# Sheet_1.net
KiCad netlist of a schematic drawn in EasyEDA
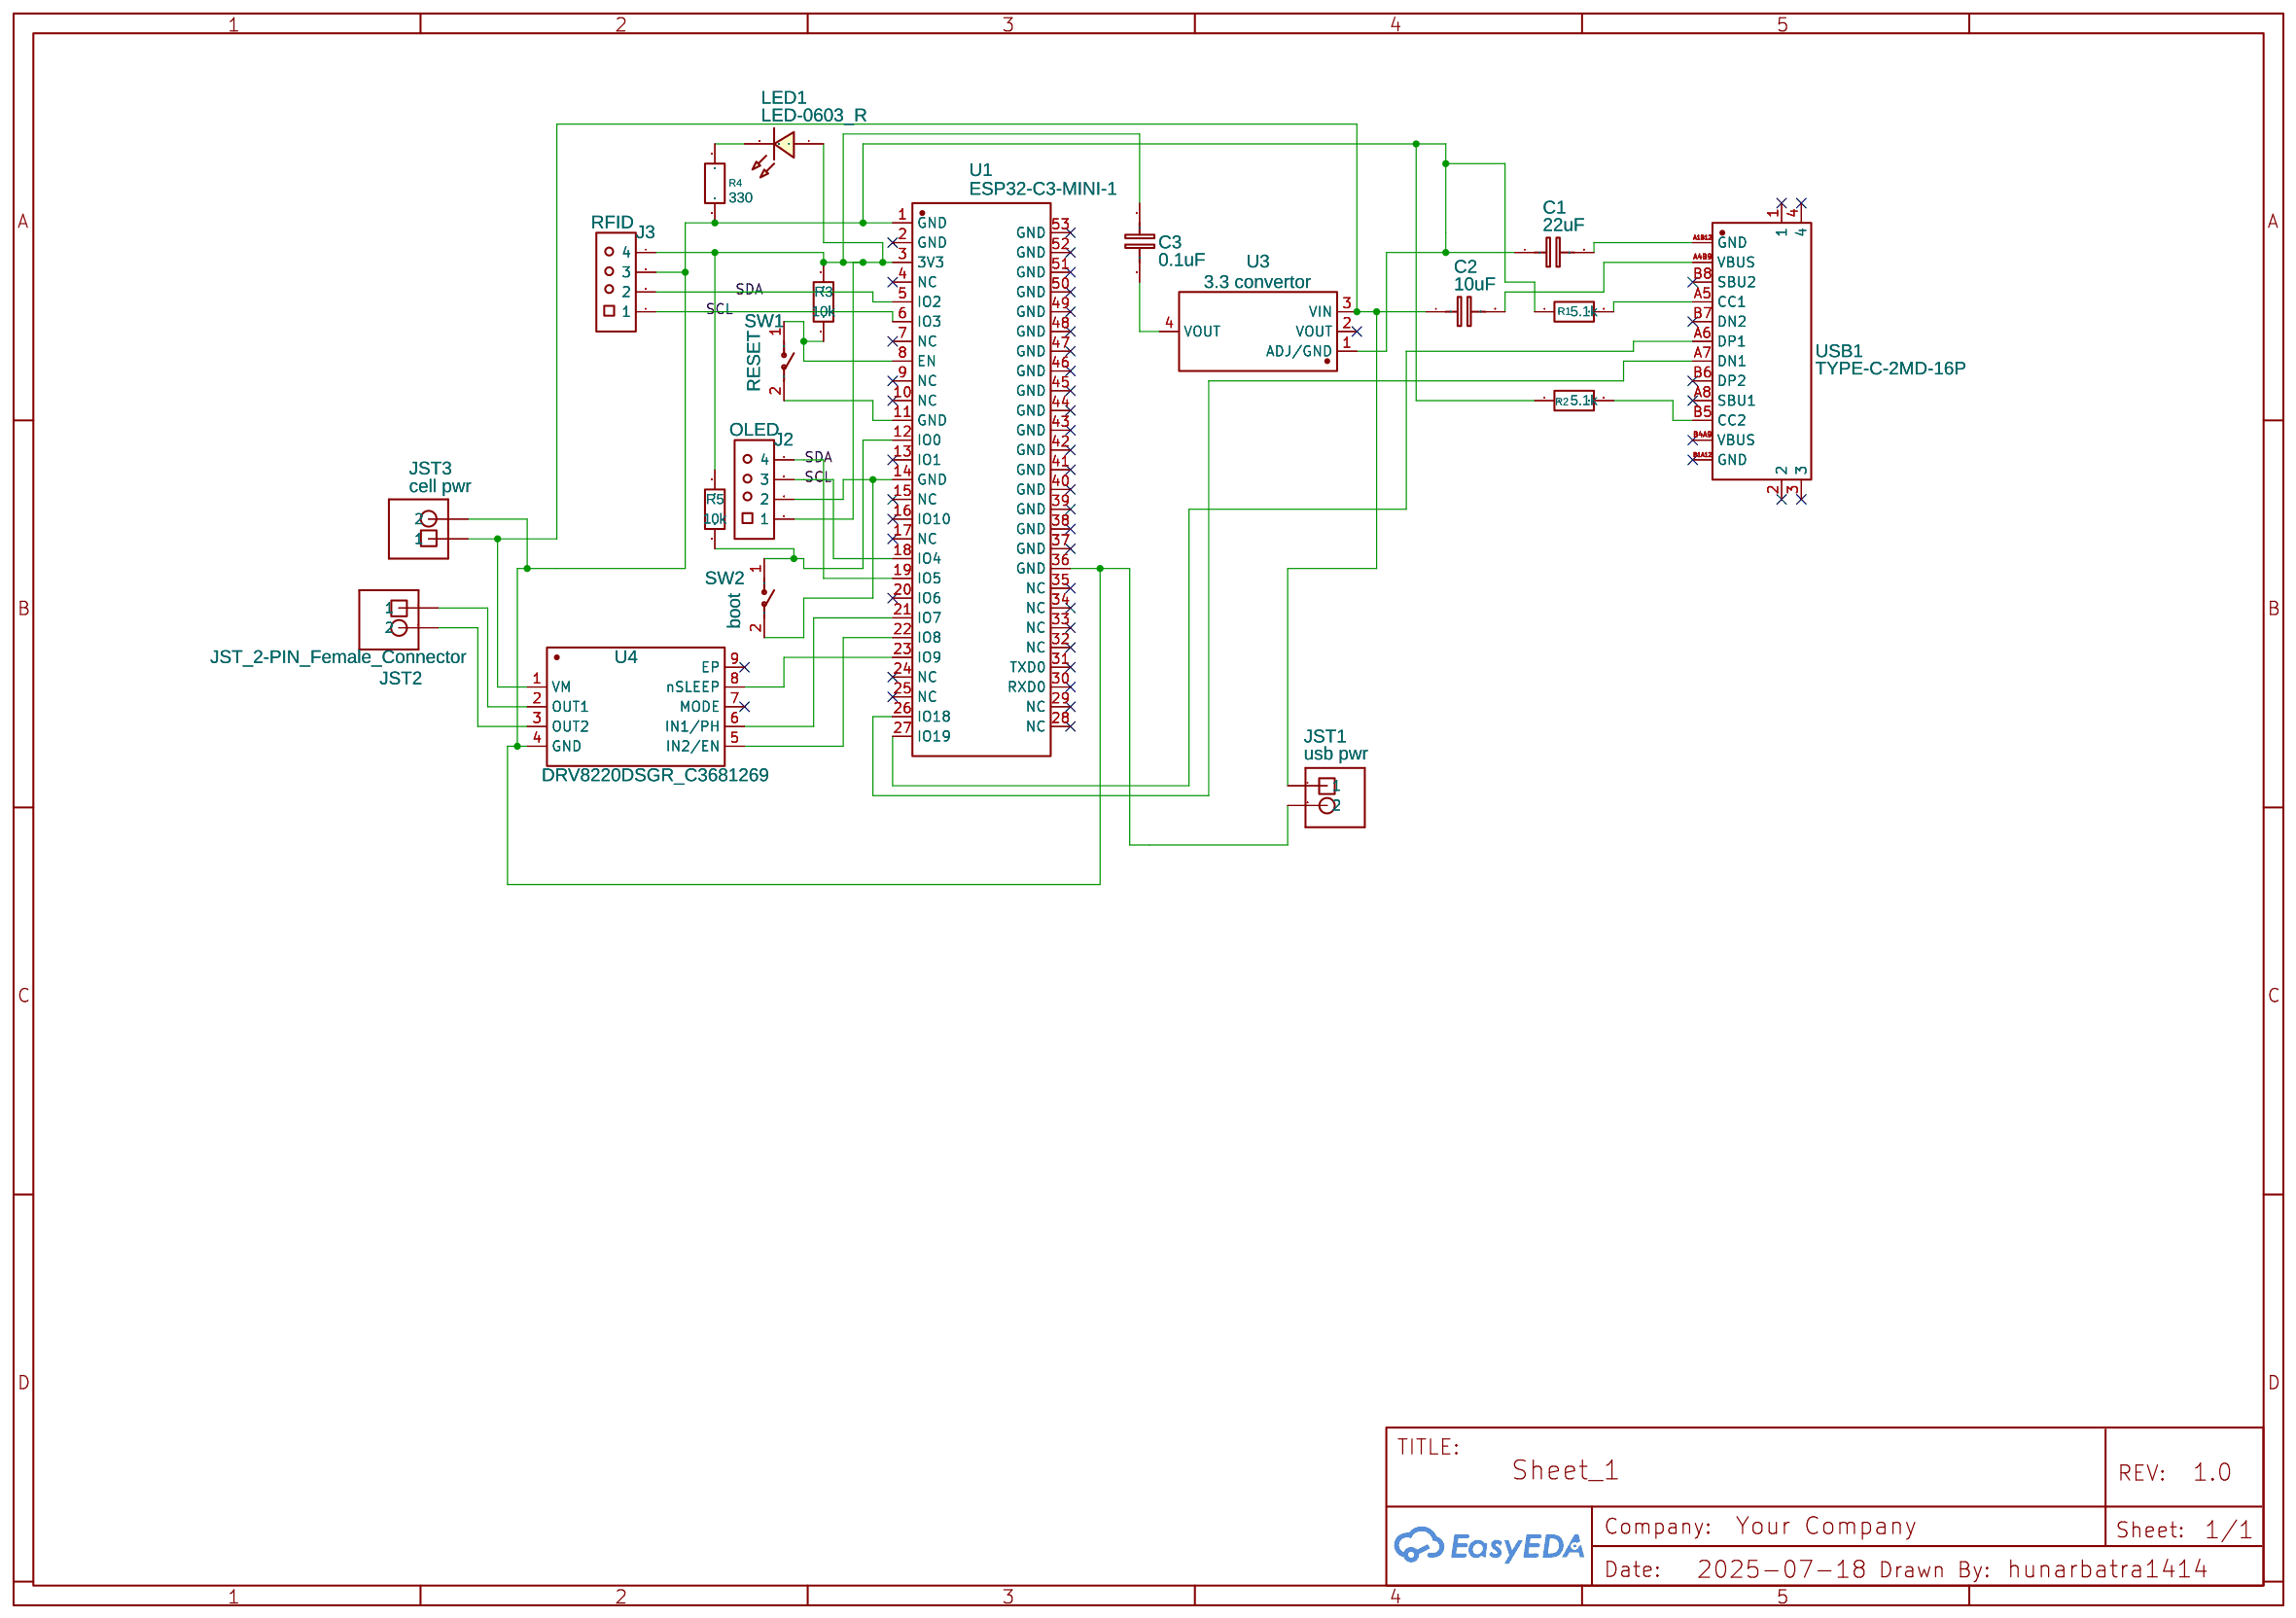
[diagram p0: schematic sheet]

(export (version "E")
  (design (tool "Eeschema 10.0.6"))
  (components
    (comp (ref "C1") (value "22uF") (libsource (lib "") (part "C_0603_EU")))
    (comp (ref "C2") (value "10uF") (libsource (lib "") (part "C_0603_EU")))
    (comp (ref "C3") (value "0.1uF") (libsource (lib "") (part "C_0603_EU_1")))
    (comp (ref "J2") (value "OLED") (libsource (lib "") (part "JST-4PIN_2.54MM")))
    (comp (ref "J3") (value "RFID") (libsource (lib "") (part "JST-4PIN_2.54MM")))
    (comp (ref "JST1") (value "usb pwr") (libsource (lib "") (part "JST_2-PIN_Female_Connector")))
    (comp (ref "JST2")
      (value "JST_2-PIN_Female_Connector")
      (libsource (lib "") (part "JST_2-PIN_Female_Connector_1"))
    )
    (comp (ref "JST3") (value "cell pwr") (libsource (lib "") (part "JST_2-PIN_Female_Connector_2")))
    (comp (ref "LED1")
      (value "LED-0603_R")
      (fields
        (field (name "Manufacturer Part") "19-217/R6C-AL1M2VY/3T")
        (field (name "Manufacturer") "EVERLIGHT(台湾亿光)")
      )
      (libsource (lib "") (part "LED-0603_R"))
    )
    (comp (ref "R1") (value "5.1k") (libsource (lib "") (part "R_0603_EU_1")))
    (comp (ref "R2") (value "5.1k") (libsource (lib "") (part "R_0603_EU_1")))
    (comp (ref "R3") (value "10k") (libsource (lib "") (part "R_0603_EU")))
    (comp (ref "R4") (value "330") (libsource (lib "") (part "R_0603_EU")))
    (comp (ref "R5") (value "10k") (libsource (lib "") (part "R_0603_EU")))
    (comp (ref "SW1")
      (value "RESET")
      (fields
        (field (name "Manufacturer Part") "TS-3025-A-C-A")
        (field (name "Manufacturer") "XKB Connection(中国星坤)")
      )
      (libsource (lib "") (part "TS-3025-A-C-A"))
    )
    (comp (ref "SW2")
      (value "boot")
      (fields
        (field (name "Manufacturer Part") "TS-3025-A-C-A")
        (field (name "Manufacturer") "XKB Connection(中国星坤)")
      )
      (libsource (lib "") (part "TS-3025-A-C-A"))
    )
    (comp (ref "U1")
      (value "ESP32-C3-MINI-1")
      (fields (field (name "Manufacturer") "RF Crazy(智汉)"))
      (libsource (lib "") (part "ESP32-C3-MINI-1"))
    )
    (comp (ref "U3")
      (value "3.3 convertor")
      (fields (field (name "Manufacturer Part") "AMS1117-3.3") (field (name "Manufacturer") "PUOLOP(迪浦)"))
      (libsource (lib "") (part "AMS1117-3.3_C351785"))
    )
    (comp (ref "U4")
      (value "DRV8220DSGR_C3681269")
      (fields (field (name "Manufacturer Part") "DRV8220DSGR") (field (name "Manufacturer") "TI(德州仪器)"))
      (libsource (lib "") (part "DRV8220DSGR_C3681269"))
    )
    (comp (ref "USB1")
      (value "TYPE-C-2MD-16P")
      (fields (field (name "Manufacturer") "JXTCONN(聚兴泰)"))
      (libsource (lib "") (part "TYPE-C-2MD-16P"))
    )
  )
  (nets
    (net (code "1") (name "/SCL") (class "Default")
      (node (ref "J2") (pin "3") (pinfunction "3_3") (pintype "unspecified"))
      (node (ref "J3") (pin "1") (pinfunction "1_1") (pintype "unspecified"))
      (node (ref "U1") (pin "18") (pinfunction "IO4_18") (pintype "unspecified"))
      (node (ref "U1") (pin "6") (pinfunction "IO3_6") (pintype "unspecified"))
    )
    (net (code "2") (name "/SDA") (class "Default")
      (node (ref "J2") (pin "4") (pinfunction "4_4") (pintype "unspecified"))
      (node (ref "J3") (pin "2") (pinfunction "2_2") (pintype "unspecified"))
      (node (ref "U1") (pin "19") (pinfunction "IO5_19") (pintype "unspecified"))
      (node (ref "U1") (pin "5") (pinfunction "IO2_5") (pintype "unspecified"))
    )
    (net (code "3") (name "Net-(C1-Pad2)") (class "Default")
      (node (ref "C1") (pin "2") (pinfunction "2_2") (pintype "unspecified"))
      (node (ref "USB1") (pin "A1B12") (pinfunction "GND_A1B12") (pintype "unspecified"))
    )
    (net (code "4") (name "Net-(C2-Pad2)") (class "Default")
      (node (ref "C2") (pin "2") (pinfunction "2_2") (pintype "unspecified"))
      (node (ref "USB1") (pin "A4B9") (pinfunction "VBUS_A4B9") (pintype "unspecified"))
    )
    (net (code "5") (name "Net-(C3-Pad2)") (class "Default")
      (node (ref "C3") (pin "2") (pinfunction "2_2") (pintype "unspecified"))
      (node (ref "U3") (pin "4") (pinfunction "VOUT_4") (pintype "unspecified"))
    )
    (net (code "6") (name "Net-(J2-Pad2)") (class "Default")
      (node (ref "J2") (pin "2") (pinfunction "2_2") (pintype "unspecified"))
      (node (ref "SW2") (pin "2") (pinfunction "2_2") (pintype "unspecified"))
      (node (ref "U1") (pin "14") (pinfunction "GND_14") (pintype "unspecified"))
    )
    (net (code "7") (name "Net-(LED1-Pad2)") (class "Default")
      (node (ref "LED1") (pin "2") (pinfunction "2_2") (pintype "unspecified"))
      (node (ref "R4") (pin "2") (pinfunction "2_2") (pintype "unspecified"))
    )
    (net (code "8") (name "Net-(SW1-Pad2)") (class "Default")
      (node (ref "SW1") (pin "2") (pinfunction "2_2") (pintype "unspecified"))
      (node (ref "U1") (pin "11") (pinfunction "GND_11") (pintype "unspecified"))
    )
    (net (code "9") (name "Net-(U1-3V3)") (class "Default")
      (node (ref "C3") (pin "1") (pinfunction "1_1") (pintype "unspecified"))
      (node (ref "J2") (pin "1") (pinfunction "1_1") (pintype "unspecified"))
      (node (ref "J3") (pin "4") (pinfunction "4_4") (pintype "unspecified"))
      (node (ref "LED1") (pin "1") (pinfunction "1_1") (pintype "unspecified"))
      (node (ref "R3") (pin "2") (pinfunction "2_2") (pintype "unspecified"))
      (node (ref "R5") (pin "2") (pinfunction "2_2") (pintype "unspecified"))
      (node (ref "U1") (pin "3") (pinfunction "3V3_3") (pintype "unspecified"))
    )
    (net (code "10") (name "Net-(U1-EN)") (class "Default")
      (node (ref "R3") (pin "1") (pinfunction "1_1") (pintype "unspecified"))
      (node (ref "SW1") (pin "1") (pinfunction "1_1") (pintype "unspecified"))
      (node (ref "U1") (pin "8") (pinfunction "EN_8") (pintype "unspecified"))
    )
    (net (code "11") (name "Net-(U1-IO0)") (class "Default")
      (node (ref "R5") (pin "1") (pinfunction "1_1") (pintype "unspecified"))
      (node (ref "SW2") (pin "1") (pinfunction "1_1") (pintype "unspecified"))
      (node (ref "U1") (pin "12") (pinfunction "IO0_12") (pintype "unspecified"))
    )
    (net (code "12") (name "Net-(U1-IO7)") (class "Default")
      (node (ref "U1") (pin "21") (pinfunction "IO7_21") (pintype "unspecified"))
      (node (ref "U4") (pin "6") (pinfunction "IN1/PH_6") (pintype "unspecified"))
    )
    (net (code "13") (name "Net-(U1-IO8)") (class "Default")
      (node (ref "U1") (pin "22") (pinfunction "IO8_22") (pintype "unspecified"))
      (node (ref "U4") (pin "5") (pinfunction "IN2/EN_5") (pintype "unspecified"))
    )
    (net (code "14") (name "Net-(U1-IO9)") (class "Default")
      (node (ref "U1") (pin "23") (pinfunction "IO9_23") (pintype "unspecified"))
      (node (ref "U4") (pin "8") (pinfunction "nSLEEP_8") (pintype "unspecified"))
    )
    (net (code "15") (name "Net-(U1-IO18)") (class "Default")
      (node (ref "U1") (pin "26") (pinfunction "IO18_26") (pintype "unspecified"))
      (node (ref "USB1") (pin "A7") (pinfunction "DN1_A7") (pintype "unspecified"))
    )
    (net (code "16") (name "Net-(U1-IO19)") (class "Default")
      (node (ref "U1") (pin "27") (pinfunction "IO19_27") (pintype "unspecified"))
      (node (ref "USB1") (pin "A6") (pinfunction "DP1_A6") (pintype "unspecified"))
    )
    (net (code "17") (name "Net-(U3-ADJ{slash}GND)") (class "Default")
      (node (ref "C1") (pin "1") (pinfunction "1_1") (pintype "unspecified"))
      (node (ref "J3") (pin "3") (pinfunction "3_3") (pintype "unspecified"))
      (node (ref "JST1") (pin "2") (pinfunction "2_2") (pintype "unspecified"))
      (node (ref "JST3") (pin "2") (pinfunction "2_2") (pintype "unspecified"))
      (node (ref "R1") (pin "1") (pinfunction "1_1") (pintype "unspecified"))
      (node (ref "R2") (pin "1") (pinfunction "1_1") (pintype "unspecified"))
      (node (ref "R4") (pin "1") (pinfunction "1_1") (pintype "unspecified"))
      (node (ref "U1") (pin "1") (pinfunction "GND_1") (pintype "unspecified"))
      (node (ref "U1") (pin "36") (pinfunction "GND_36") (pintype "unspecified"))
      (node (ref "U3") (pin "1") (pinfunction "ADJ/GND_1") (pintype "unspecified"))
      (node (ref "U4") (pin "4") (pinfunction "GND_4") (pintype "unspecified"))
    )
    (net (code "18") (name "Net-(U3-VIN)") (class "Default")
      (node (ref "C2") (pin "1") (pinfunction "1_1") (pintype "unspecified"))
      (node (ref "JST1") (pin "1") (pinfunction "1_1") (pintype "unspecified"))
      (node (ref "JST3") (pin "1") (pinfunction "1_1") (pintype "unspecified"))
      (node (ref "U3") (pin "3") (pinfunction "VIN_3") (pintype "unspecified"))
      (node (ref "U4") (pin "1") (pinfunction "VM_1") (pintype "unspecified"))
    )
    (net (code "19") (name "Net-(U4-OUT1)") (class "Default")
      (node (ref "JST2") (pin "1") (pinfunction "1_1") (pintype "unspecified"))
      (node (ref "U4") (pin "2") (pinfunction "OUT1_2") (pintype "unspecified"))
    )
    (net (code "20") (name "Net-(U4-OUT2)") (class "Default")
      (node (ref "JST2") (pin "2") (pinfunction "2_2") (pintype "unspecified"))
      (node (ref "U4") (pin "3") (pinfunction "OUT2_3") (pintype "unspecified"))
    )
    (net (code "21") (name "Net-(USB1-CC1)") (class "Default")
      (node (ref "R1") (pin "2") (pinfunction "2_2") (pintype "unspecified"))
      (node (ref "USB1") (pin "A5") (pinfunction "CC1_A5") (pintype "unspecified"))
    )
    (net (code "22") (name "Net-(USB1-CC2)") (class "Default")
      (node (ref "R2") (pin "2") (pinfunction "2_2") (pintype "unspecified"))
      (node (ref "USB1") (pin "B5") (pinfunction "CC2_B5") (pintype "unspecified"))
    )
    (net (code "23") (name "unconnected-(U1-GND-Pad2)") (class "Default")
      (node (ref "U1") (pin "2") (pinfunction "GND_2") (pintype "unspecified+no_connect"))
    )
    (net (code "24") (name "unconnected-(U1-GND-Pad37)") (class "Default")
      (node (ref "U1") (pin "37") (pinfunction "GND_37") (pintype "unspecified+no_connect"))
    )
    (net (code "25") (name "unconnected-(U1-GND-Pad38)") (class "Default")
      (node (ref "U1") (pin "38") (pinfunction "GND_38") (pintype "unspecified+no_connect"))
    )
    (net (code "26") (name "unconnected-(U1-GND-Pad39)") (class "Default")
      (node (ref "U1") (pin "39") (pinfunction "GND_39") (pintype "unspecified+no_connect"))
    )
    (net (code "27") (name "unconnected-(U1-GND-Pad40)") (class "Default")
      (node (ref "U1") (pin "40") (pinfunction "GND_40") (pintype "unspecified+no_connect"))
    )
    (net (code "28") (name "unconnected-(U1-GND-Pad41)") (class "Default")
      (node (ref "U1") (pin "41") (pinfunction "GND_41") (pintype "unspecified+no_connect"))
    )
    (net (code "29") (name "unconnected-(U1-GND-Pad42)") (class "Default")
      (node (ref "U1") (pin "42") (pinfunction "GND_42") (pintype "unspecified+no_connect"))
    )
    (net (code "30") (name "unconnected-(U1-GND-Pad43)") (class "Default")
      (node (ref "U1") (pin "43") (pinfunction "GND_43") (pintype "unspecified+no_connect"))
    )
    (net (code "31") (name "unconnected-(U1-GND-Pad44)") (class "Default")
      (node (ref "U1") (pin "44") (pinfunction "GND_44") (pintype "unspecified+no_connect"))
    )
    (net (code "32") (name "unconnected-(U1-GND-Pad45)") (class "Default")
      (node (ref "U1") (pin "45") (pinfunction "GND_45") (pintype "unspecified+no_connect"))
    )
    (net (code "33") (name "unconnected-(U1-GND-Pad46)") (class "Default")
      (node (ref "U1") (pin "46") (pinfunction "GND_46") (pintype "unspecified+no_connect"))
    )
    (net (code "34") (name "unconnected-(U1-GND-Pad47)") (class "Default")
      (node (ref "U1") (pin "47") (pinfunction "GND_47") (pintype "unspecified+no_connect"))
    )
    (net (code "35") (name "unconnected-(U1-GND-Pad48)") (class "Default")
      (node (ref "U1") (pin "48") (pinfunction "GND_48") (pintype "unspecified+no_connect"))
    )
    (net (code "36") (name "unconnected-(U1-GND-Pad49)") (class "Default")
      (node (ref "U1") (pin "49") (pinfunction "GND_49") (pintype "unspecified+no_connect"))
    )
    (net (code "37") (name "unconnected-(U1-GND-Pad50)") (class "Default")
      (node (ref "U1") (pin "50") (pinfunction "GND_50") (pintype "unspecified+no_connect"))
    )
    (net (code "38") (name "unconnected-(U1-GND-Pad51)") (class "Default")
      (node (ref "U1") (pin "51") (pinfunction "GND_51") (pintype "unspecified+no_connect"))
    )
    (net (code "39") (name "unconnected-(U1-GND-Pad52)") (class "Default")
      (node (ref "U1") (pin "52") (pinfunction "GND_52") (pintype "unspecified+no_connect"))
    )
    (net (code "40") (name "unconnected-(U1-GND-Pad53)") (class "Default")
      (node (ref "U1") (pin "53") (pinfunction "GND_53") (pintype "unspecified+no_connect"))
    )
    (net (code "41") (name "unconnected-(U1-IO1-Pad13)") (class "Default")
      (node (ref "U1") (pin "13") (pinfunction "IO1_13") (pintype "unspecified+no_connect"))
    )
    (net (code "42") (name "unconnected-(U1-IO6-Pad20)") (class "Default")
      (node (ref "U1") (pin "20") (pinfunction "IO6_20") (pintype "unspecified+no_connect"))
    )
    (net (code "43") (name "unconnected-(U1-IO10-Pad16)") (class "Default")
      (node (ref "U1") (pin "16") (pinfunction "IO10_16") (pintype "unspecified+no_connect"))
    )
    (net (code "44") (name "unconnected-(U1-NC-Pad4)") (class "Default")
      (node (ref "U1") (pin "4") (pinfunction "NC_4") (pintype "unspecified+no_connect"))
    )
    (net (code "45") (name "unconnected-(U1-NC-Pad7)") (class "Default")
      (node (ref "U1") (pin "7") (pinfunction "NC_7") (pintype "unspecified+no_connect"))
    )
    (net (code "46") (name "unconnected-(U1-NC-Pad9)") (class "Default")
      (node (ref "U1") (pin "9") (pinfunction "NC_9") (pintype "unspecified+no_connect"))
    )
    (net (code "47") (name "unconnected-(U1-NC-Pad10)") (class "Default")
      (node (ref "U1") (pin "10") (pinfunction "NC_10") (pintype "unspecified+no_connect"))
    )
    (net (code "48") (name "unconnected-(U1-NC-Pad15)") (class "Default")
      (node (ref "U1") (pin "15") (pinfunction "NC_15") (pintype "unspecified+no_connect"))
    )
    (net (code "49") (name "unconnected-(U1-NC-Pad17)") (class "Default")
      (node (ref "U1") (pin "17") (pinfunction "NC_17") (pintype "unspecified+no_connect"))
    )
    (net (code "50") (name "unconnected-(U1-NC-Pad24)") (class "Default")
      (node (ref "U1") (pin "24") (pinfunction "NC_24") (pintype "unspecified+no_connect"))
    )
    (net (code "51") (name "unconnected-(U1-NC-Pad25)") (class "Default")
      (node (ref "U1") (pin "25") (pinfunction "NC_25") (pintype "unspecified+no_connect"))
    )
    (net (code "52") (name "unconnected-(U1-NC-Pad28)") (class "Default")
      (node (ref "U1") (pin "28") (pinfunction "NC_28") (pintype "unspecified+no_connect"))
    )
    (net (code "53") (name "unconnected-(U1-NC-Pad29)") (class "Default")
      (node (ref "U1") (pin "29") (pinfunction "NC_29") (pintype "unspecified+no_connect"))
    )
    (net (code "54") (name "unconnected-(U1-NC-Pad32)") (class "Default")
      (node (ref "U1") (pin "32") (pinfunction "NC_32") (pintype "unspecified+no_connect"))
    )
    (net (code "55") (name "unconnected-(U1-NC-Pad33)") (class "Default")
      (node (ref "U1") (pin "33") (pinfunction "NC_33") (pintype "unspecified+no_connect"))
    )
    (net (code "56") (name "unconnected-(U1-NC-Pad34)") (class "Default")
      (node (ref "U1") (pin "34") (pinfunction "NC_34") (pintype "unspecified+no_connect"))
    )
    (net (code "57") (name "unconnected-(U1-NC-Pad35)") (class "Default")
      (node (ref "U1") (pin "35") (pinfunction "NC_35") (pintype "unspecified+no_connect"))
    )
    (net (code "58") (name "unconnected-(U1-RXD0-Pad30)") (class "Default")
      (node (ref "U1") (pin "30") (pinfunction "RXD0_30") (pintype "unspecified+no_connect"))
    )
    (net (code "59") (name "unconnected-(U1-TXD0-Pad31)") (class "Default")
      (node (ref "U1") (pin "31") (pinfunction "TXD0_31") (pintype "unspecified+no_connect"))
    )
    (net (code "60") (name "unconnected-(U3-VOUT-Pad2)") (class "Default")
      (node (ref "U3") (pin "2") (pinfunction "VOUT_2") (pintype "unspecified+no_connect"))
    )
    (net (code "61") (name "unconnected-(U4-EP-Pad9)") (class "Default")
      (node (ref "U4") (pin "9") (pinfunction "EP_9") (pintype "unspecified+no_connect"))
    )
    (net (code "62") (name "unconnected-(U4-MODE-Pad7)") (class "Default")
      (node (ref "U4") (pin "7") (pinfunction "MODE_7") (pintype "unspecified+no_connect"))
    )
    (net (code "63") (name "unconnected-(USB1-DN2-PadB7)") (class "Default")
      (node (ref "USB1") (pin "B7") (pinfunction "DN2_B7") (pintype "unspecified+no_connect"))
    )
    (net (code "64") (name "unconnected-(USB1-DP2-PadB6)") (class "Default")
      (node (ref "USB1") (pin "B6") (pinfunction "DP2_B6") (pintype "unspecified+no_connect"))
    )
    (net (code "65") (name "unconnected-(USB1-GND-PadB1A12)") (class "Default")
      (node (ref "USB1") (pin "B1A12") (pinfunction "GND_B1A12") (pintype "unspecified+no_connect"))
    )
    (net (code "66") (name "unconnected-(USB1-Pad1)") (class "Default")
      (node (ref "USB1") (pin "1") (pinfunction "1_1") (pintype "unspecified+no_connect"))
    )
    (net (code "67") (name "unconnected-(USB1-Pad2)") (class "Default")
      (node (ref "USB1") (pin "2") (pinfunction "2_2") (pintype "unspecified+no_connect"))
    )
    (net (code "68") (name "unconnected-(USB1-Pad3)") (class "Default")
      (node (ref "USB1") (pin "3") (pinfunction "3_3") (pintype "unspecified+no_connect"))
    )
    (net (code "69") (name "unconnected-(USB1-Pad4)") (class "Default")
      (node (ref "USB1") (pin "4") (pinfunction "4_4") (pintype "unspecified+no_connect"))
    )
    (net (code "70") (name "unconnected-(USB1-SBU1-PadA8)") (class "Default")
      (node (ref "USB1") (pin "A8") (pinfunction "SBU1_A8") (pintype "unspecified+no_connect"))
    )
    (net (code "71") (name "unconnected-(USB1-SBU2-PadB8)") (class "Default")
      (node (ref "USB1") (pin "B8") (pinfunction "SBU2_B8") (pintype "unspecified+no_connect"))
    )
    (net (code "72") (name "unconnected-(USB1-VBUS-PadB4A9)") (class "Default")
      (node (ref "USB1") (pin "B4A9") (pinfunction "VBUS_B4A9") (pintype "unspecified+no_connect"))
    )
  )
)
